# 01_ESP-CAM.net
KiCad netlist of a schematic drawn in Altium Designer
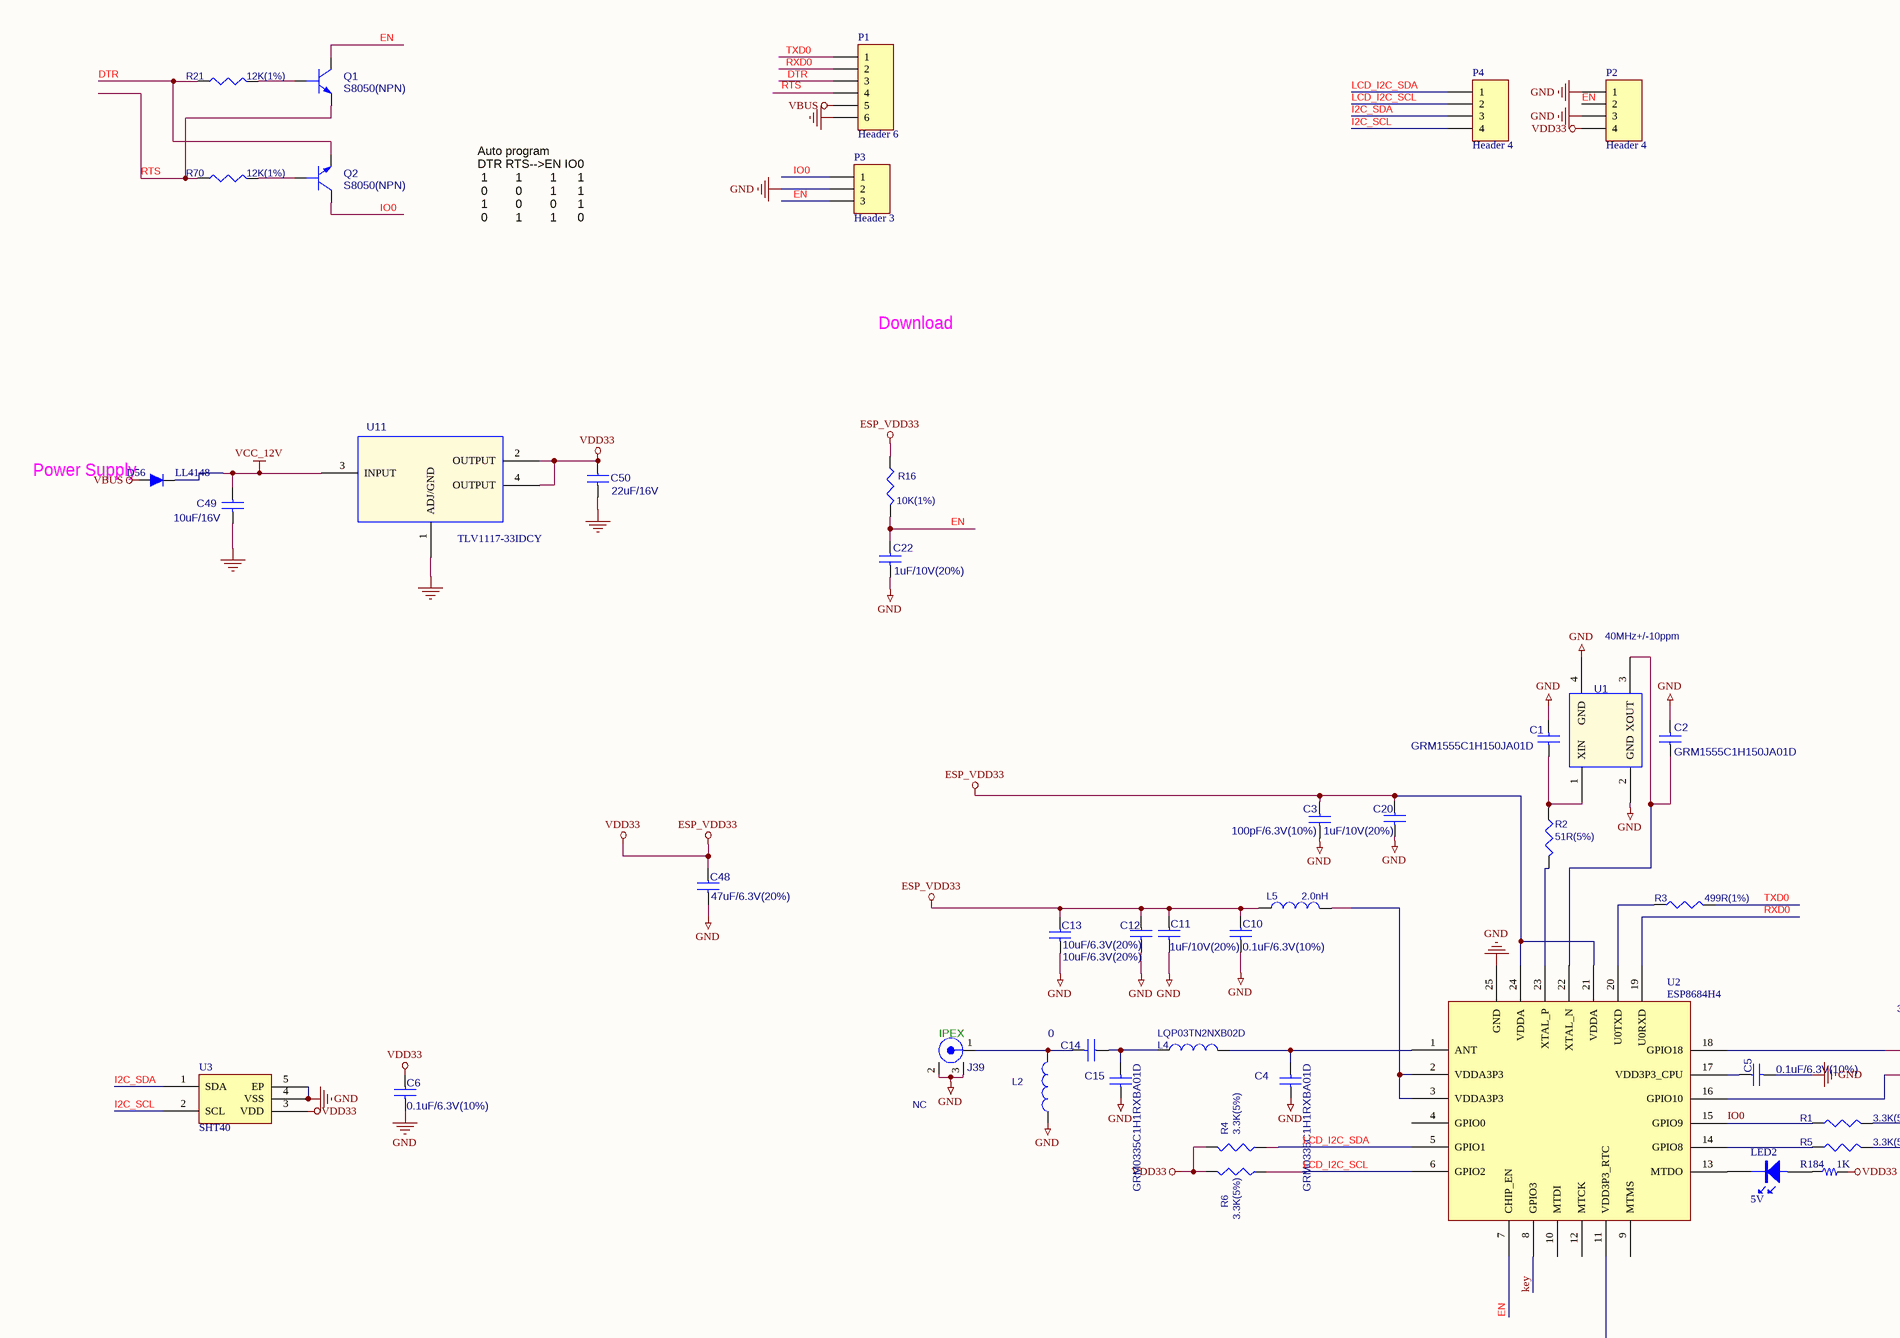
[diagram p0: 01_ESP-CAM.SchDoc, top left]
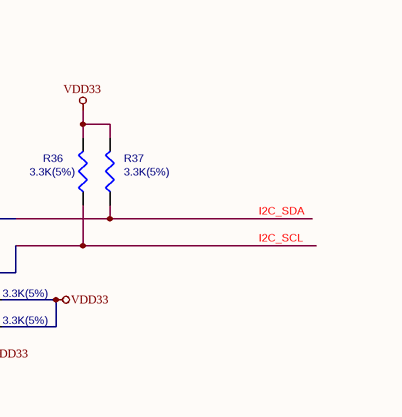
[diagram p1: 01_ESP-CAM.SchDoc, top right]
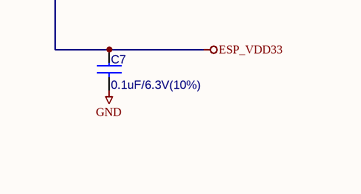
[diagram p2: 01_ESP-CAM.SchDoc, bottom left]
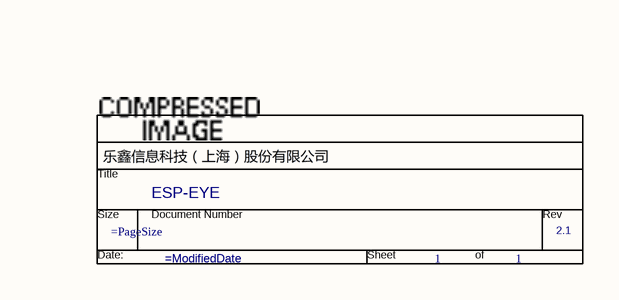
[diagram p3: 01_ESP-CAM.SchDoc, bottom right]

(export (version "E")
  (design (tool "Eeschema 10.0.6"))
  (components
    (comp (ref "*")
      (value "~")
      (fields
        (field (name "REVCODE") "2.1")
        (field (name "TITLE") "ESP-EYE")
        (field (name "PAGE NUMBER") "1")
        (field (name "PAGE COUNT") "1")
      )
      (libsource (lib "*") (part "espTitleBlock1"))
    )
    (comp (ref "C1")
      (value "GRM1555C1H150JA01D")
      (footprint "0402C")
      (fields (field (name "Comment") "CAP NP_Dup1"))
      (libsource (lib "*") (part "CAP NP_Dup1"))
    )
    (comp (ref "C2")
      (value "GRM1555C1H150JA01D")
      (footprint "0402C")
      (fields (field (name "Comment") "CAP NP_Dup1"))
      (libsource (lib "*") (part "CAP NP_Dup1"))
    )
    (comp (ref "C3")
      (value "100pF/6.3V(10%)")
      (footprint "0402C")
      (fields (field (name "Comment") "CAP NP_Dup1"))
      (libsource (lib "*") (part "CAP NP_Dup1"))
    )
    (comp (ref "C4")
      (value "GRM0335C1H1RXBA01D")
      (footprint "0402C")
      (fields (field (name "Comment") "CAP NP_Dup1"))
      (libsource (lib "*") (part "CAP NP_Dup1"))
    )
    (comp (ref "C5")
      (value "0.1uF/6.3V(10%)")
      (footprint "0402C")
      (fields (field (name "Comment") "CAP NP_Dup1"))
      (libsource (lib "*") (part "CAP NP_Dup1"))
    )
    (comp (ref "C6")
      (value "0.1uF/6.3V(10%)")
      (footprint "0402C")
      (fields (field (name "Comment") "CAP NP_Dup1"))
      (libsource (lib "*") (part "CAP NP_Dup1"))
    )
    (comp (ref "C7")
      (value "0.1uF/6.3V(10%)")
      (footprint "0402C")
      (fields (field (name "Comment") "CAP NP_Dup1"))
      (libsource (lib "*") (part "CAP NP_Dup1"))
    )
    (comp (ref "C10")
      (value "0.1uF/6.3V(10%)")
      (footprint "0402C")
      (fields (field (name "Comment") "CAP NP_Dup1"))
      (libsource (lib "*") (part "CAP NP_Dup1"))
    )
    (comp (ref "C11")
      (value "1uF/10V(20%)")
      (footprint "0402C")
      (fields (field (name "Comment") "CAP NP_Dup1"))
      (libsource (lib "*") (part "CAP NP_Dup1"))
    )
    (comp (ref "C12")
      (value "10uF/6.3V(20%)")
      (footprint "0402C")
      (fields (field (name "Comment") "CAP NP_Dup1"))
      (libsource (lib "*") (part "CAP NP_Dup1"))
    )
    (comp (ref "C13")
      (value "10uF/6.3V(20%)")
      (footprint "0402C")
      (fields (field (name "Comment") "CAP NP_Dup1"))
      (libsource (lib "*") (part "CAP NP_Dup1"))
    )
    (comp (ref "C14")
      (value "0")
      (footprint "0402C")
      (fields (field (name "Comment") "CAP NP_Dup1"))
      (libsource (lib "*") (part "CAP NP_Dup1"))
    )
    (comp (ref "C15")
      (value "GRM0335C1H1RXBA01D")
      (footprint "0402C")
      (fields (field (name "Comment") "CAP NP_Dup1"))
      (libsource (lib "*") (part "CAP NP_Dup1"))
    )
    (comp (ref "C20")
      (value "1uF/10V(20%)")
      (footprint "0402C")
      (fields (field (name "Comment") "CAP NP_Dup1"))
      (libsource (lib "*") (part "CAP NP_Dup1"))
    )
    (comp (ref "C22")
      (value "1uF/10V(20%)")
      (footprint "0402C")
      (fields (field (name "Comment") "CAP NP_Dup1"))
      (libsource (lib "*") (part "CAP NP_Dup1"))
    )
    (comp (ref "C48")
      (value "47uF/6.3V(20%)")
      (footprint "1206C")
      (fields (field (name "Comment") "CAP NP_Dup1"))
      (libsource (lib "*") (part "CAP NP_Dup1"))
    )
    (comp (ref "C49")
      (value "10uF/16V")
      (footprint "0603C")
      (fields (field (name "Comment") "CAP NP"))
      (libsource (lib "*") (part "CAP NP"))
    )
    (comp (ref "C50")
      (value "22uF/16V")
      (footprint "1206C")
      (fields (field (name "Comment") "CAP NP"))
      (libsource (lib "*") (part "CAP NP"))
    )
    (comp (ref "D56")
      (value "LL4148")
      (footprint "sod123")
      (description "VISHAY,LL4148,圆柱体MiniMELF100V/2A,ROHS")
      (libsource (lib "Device2018") (part "LL4148"))
    )
    (comp (ref "J39")
      (value "IPEX")
      (footprint "IPEX-SMD_BWIPX-1-001E")
      (fields (field (name "Comment") "IPEX_0"))
      (libsource (lib "*") (part "IPEX_0"))
    )
    (comp (ref "L2")
      (value "NC")
      (footprint "0402R")
      (fields (field (name "Comment") "CHOKE"))
      (libsource (lib "") (part "CHOKE_1"))
    )
    (comp (ref "L4")
      (value "LQP03TN2NXB02D")
      (footprint "0402R")
      (fields (field (name "Comment") "CHOKE"))
      (libsource (lib "*") (part "CHOKE"))
    )
    (comp (ref "L5")
      (value "2.0nH")
      (footprint "0402R")
      (fields (field (name "Comment") "CHOKE"))
      (libsource (lib "") (part "CHOKE_1"))
    )
    (comp (ref "LED2") (value "5V") (footprint "0603LED") (libsource (lib "*") (part "LED")))
    (comp (ref "P1")
      (value "Header 6")
      (footprint "HDR1X6")
      (description "Header, 6-Pin")
      (fields (field (name "PUBLISHER") "Altium Limited"))
      (libsource (lib "Miscellaneous Connectors") (part "Header 6"))
    )
    (comp (ref "P2")
      (value "Header 4")
      (footprint "1.27-4P")
      (description "Header, 4-Pin")
      (fields (field (name "PUBLISHER") "Altium Limited"))
      (libsource (lib "Miscellaneous Connectors") (part "Header 4"))
    )
    (comp (ref "P3")
      (value "Header 3")
      (footprint "HDR1X3")
      (description "Header, 3-Pin")
      (fields (field (name "PUBLISHER") "Altium Limited"))
      (libsource (lib "Miscellaneous Connectors") (part "Header 3"))
    )
    (comp (ref "P4")
      (value "Header 4")
      (footprint "1.27-4P")
      (description "Header, 4-Pin")
      (fields (field (name "PUBLISHER") "Altium Limited"))
      (libsource (lib "Miscellaneous Connectors") (part "Header 4"))
    )
    (comp (ref "Q1")
      (value "S8050(NPN)")
      (footprint "SOT23-3")
      (fields (field (name "Comment") "NPN BCE_2"))
      (libsource (lib "*") (part "NPN BCE_2"))
    )
    (comp (ref "Q2")
      (value "S8050(NPN)")
      (footprint "SOT23-3")
      (fields (field (name "Comment") "NPN BCE_2"))
      (libsource (lib "*") (part "NPN BCE_2"))
    )
    (comp (ref "R1")
      (value "3.3K(5%)")
      (footprint "0402R")
      (fields (field (name "Comment") "RESISTOR_0"))
      (libsource (lib "*") (part "RESISTOR_0"))
    )
    (comp (ref "R2")
      (value "51R(5%)")
      (footprint "0402R")
      (fields (field (name "Comment") "RESISTOR"))
      (libsource (lib "*") (part "RESISTOR"))
    )
    (comp (ref "R3")
      (value "499R(1%)")
      (footprint "0402R")
      (fields (field (name "Comment") "RESISTOR"))
      (libsource (lib "*") (part "RESISTOR"))
    )
    (comp (ref "R4")
      (value "3.3K(5%)")
      (footprint "0402R")
      (fields (field (name "Comment") "RESISTOR_0"))
      (libsource (lib "*") (part "RESISTOR_0"))
    )
    (comp (ref "R5")
      (value "3.3K(5%)")
      (footprint "0402R")
      (fields (field (name "Comment") "RESISTOR_0"))
      (libsource (lib "*") (part "RESISTOR_0"))
    )
    (comp (ref "R6")
      (value "3.3K(5%)")
      (footprint "0402R")
      (fields (field (name "Comment") "RESISTOR_0"))
      (libsource (lib "*") (part "RESISTOR_0"))
    )
    (comp (ref "R16")
      (value "10K(1%)")
      (footprint "0402R")
      (fields (field (name "Comment") "RESISTOR_0"))
      (libsource (lib "*") (part "RESISTOR_0"))
    )
    (comp (ref "R21")
      (value "12K(1%)")
      (footprint "0402R")
      (fields (field (name "Comment") "RESISTOR_0"))
      (libsource (lib "*") (part "RESISTOR_0"))
    )
    (comp (ref "R36")
      (value "3.3K(5%)")
      (footprint "0402R")
      (fields (field (name "Comment") "RESISTOR_0"))
      (libsource (lib "*") (part "RESISTOR_0"))
    )
    (comp (ref "R37")
      (value "3.3K(5%)")
      (footprint "0402R")
      (fields (field (name "Comment") "RESISTOR_0"))
      (libsource (lib "*") (part "RESISTOR_0"))
    )
    (comp (ref "R70")
      (value "12K(1%)")
      (footprint "0402R")
      (fields (field (name "Comment") "RESISTOR_0"))
      (libsource (lib "*") (part "RESISTOR_0"))
    )
    (comp (ref "R184")
      (value "1K")
      (footprint "0603R")
      (description "R")
      (libsource (lib "JRJ_1") (part "R"))
    )
    (comp (ref "U1")
      (value "40MHz+/-10ppm")
      (footprint "XTAL4TN_3225")
      (fields (field (name "Comment") "X1_1"))
      (libsource (lib "*") (part "X1_1"))
    )
    (comp (ref "U2")
      (value "ESP8684H4")
      (footprint "QFN24-MPU6000")
      (libsource (lib "Schlib_20110825") (part "ESP8684H4"))
    )
    (comp (ref "U3") (value "SHT40") (footprint "SH30") (libsource (lib "Schlib_20110825") (part "SHT40")))
    (comp (ref "U11")
      (value "TLV1117-33IDCY")
      (footprint "SOT223")
      (fields (field (name "Comment") "TLV1117"))
      (libsource (lib "*") (part "TLV1117-33IDCY"))
    )
  )
  (nets
    (net (code "1") (name "/DTR") (class "Default")
      (node (ref "P1") (pin "3") (pinfunction "3_3") (pintype "passive"))
      (node (ref "Q2") (pin "2") (pinfunction "E_2") (pintype "passive"))
      (node (ref "R21") (pin "1") (pinfunction "1_1") (pintype "passive"))
    )
    (net (code "2") (name "/EN") (class "Default")
      (node (ref "C22") (pin "1") (pinfunction "1_1") (pintype "passive"))
      (node (ref "P2") (pin "2") (pinfunction "2_2") (pintype "passive"))
      (node (ref "P3") (pin "3") (pinfunction "3_3") (pintype "passive"))
      (node (ref "Q1") (pin "3") (pinfunction "C_3") (pintype "passive"))
      (node (ref "R16") (pin "2") (pinfunction "2_2") (pintype "passive"))
      (node (ref "U2") (pin "7") (pinfunction "CHIP_EN_7") (pintype "passive"))
    )
    (net (code "3") (name "/I2C_SCL") (class "Default")
      (node (ref "P4") (pin "4") (pinfunction "4_4") (pintype "passive"))
      (node (ref "R36") (pin "1") (pinfunction "1_1") (pintype "passive"))
      (node (ref "U2") (pin "16") (pinfunction "GPIO10_16") (pintype "passive"))
      (node (ref "U3") (pin "2") (pinfunction "SCL_2") (pintype "passive"))
    )
    (net (code "4") (name "/I2C_SDA") (class "Default")
      (node (ref "P4") (pin "3") (pinfunction "3_3") (pintype "passive"))
      (node (ref "R37") (pin "1") (pinfunction "1_1") (pintype "passive"))
      (node (ref "U2") (pin "18") (pinfunction "GPIO18_18") (pintype "passive"))
      (node (ref "U3") (pin "1") (pinfunction "SDA_1") (pintype "passive"))
    )
    (net (code "5") (name "/IO0") (class "Default")
      (node (ref "P3") (pin "1") (pinfunction "1_1") (pintype "passive"))
      (node (ref "Q2") (pin "3") (pinfunction "C_3") (pintype "passive"))
      (node (ref "R1") (pin "1") (pinfunction "1_1") (pintype "passive"))
      (node (ref "U2") (pin "15") (pinfunction "GPIO9_15") (pintype "passive"))
    )
    (net (code "6") (name "/LCD_I2C_SCL") (class "Default")
      (node (ref "P4") (pin "2") (pinfunction "2_2") (pintype "passive"))
      (node (ref "R6") (pin "1") (pinfunction "1_1") (pintype "passive"))
      (node (ref "U2") (pin "6") (pinfunction "GPIO2_6") (pintype "passive"))
    )
    (net (code "7") (name "/LCD_I2C_SDA") (class "Default")
      (node (ref "P4") (pin "1") (pinfunction "1_1") (pintype "passive"))
      (node (ref "R4") (pin "1") (pinfunction "1_1") (pintype "passive"))
      (node (ref "U2") (pin "5") (pinfunction "GPIO1_5") (pintype "passive"))
    )
    (net (code "8") (name "/RTS") (class "Default")
      (node (ref "Q1") (pin "2") (pinfunction "E_2") (pintype "passive"))
      (node (ref "R70") (pin "1") (pinfunction "1_1") (pintype "passive"))
    )
    (net (code "9") (name "/RXD0") (class "Default")
      (node (ref "P1") (pin "2") (pinfunction "2_2") (pintype "passive"))
      (node (ref "U2") (pin "19") (pinfunction "U0RXD_19") (pintype "passive"))
    )
    (net (code "10") (name "/TXD0") (class "Default")
      (node (ref "P1") (pin "1") (pinfunction "1_1") (pintype "passive"))
      (node (ref "R3") (pin "2") (pinfunction "2_2") (pintype "passive"))
    )
    (net (code "11") (name "/key") (class "Default")
      (node (ref "U2") (pin "8") (pinfunction "GPIO3_8") (pintype "passive"))
    )
    (net (code "12") (name "ESP_VDD33") (class "Default")
      (node (ref "C10") (pin "1") (pinfunction "1_1") (pintype "passive"))
      (node (ref "C11") (pin "1") (pinfunction "1_1") (pintype "passive"))
      (node (ref "C12") (pin "1") (pinfunction "1_1") (pintype "passive"))
      (node (ref "C13") (pin "1") (pinfunction "1_1") (pintype "passive"))
      (node (ref "C20") (pin "1") (pinfunction "1_1") (pintype "passive"))
      (node (ref "C3") (pin "1") (pinfunction "1_1") (pintype "passive"))
      (node (ref "C48") (pin "1") (pinfunction "1_1") (pintype "passive"))
      (node (ref "C50") (pin "1") (pinfunction "1_1") (pintype "passive"))
      (node (ref "C6") (pin "1") (pinfunction "1_1") (pintype "passive"))
      (node (ref "C7") (pin "1") (pinfunction "1_1") (pintype "passive"))
      (node (ref "L5") (pin "2") (pinfunction "2_2") (pintype "passive"))
      (node (ref "P2") (pin "4") (pinfunction "4_4") (pintype "passive"))
      (node (ref "R1") (pin "2") (pinfunction "2_2") (pintype "passive"))
      (node (ref "R16") (pin "1") (pinfunction "1_1") (pintype "passive"))
      (node (ref "R184") (pin "2") (pintype "passive"))
      (node (ref "R36") (pin "2") (pinfunction "2_2") (pintype "passive"))
      (node (ref "R37") (pin "2") (pinfunction "2_2") (pintype "passive"))
      (node (ref "R4") (pin "2") (pinfunction "2_2") (pintype "passive"))
      (node (ref "R5") (pin "2") (pinfunction "2_2") (pintype "passive"))
      (node (ref "R6") (pin "2") (pinfunction "2_2") (pintype "passive"))
      (node (ref "U11") (pin "2") (pinfunction "OUTPUT_2") (pintype "power_in"))
      (node (ref "U11") (pin "4") (pinfunction "OUTPUT_4") (pintype "power_in"))
      (node (ref "U2") (pin "11") (pinfunction "VDD3P3_RTC_11") (pintype "passive"))
      (node (ref "U2") (pin "21") (pinfunction "VDDA_21") (pintype "passive"))
      (node (ref "U2") (pin "24") (pinfunction "VDDA_24") (pintype "passive"))
      (node (ref "U3") (pin "3") (pinfunction "VDD_3") (pintype "passive"))
    )
    (net (code "13") (name "GND") (class "Default")
      (node (ref "C1") (pin "2") (pinfunction "2_2") (pintype "passive"))
      (node (ref "C10") (pin "2") (pinfunction "2_2") (pintype "passive"))
      (node (ref "C11") (pin "2") (pinfunction "2_2") (pintype "passive"))
      (node (ref "C12") (pin "2") (pinfunction "2_2") (pintype "passive"))
      (node (ref "C13") (pin "2") (pinfunction "2_2") (pintype "passive"))
      (node (ref "C15") (pin "1") (pinfunction "1_1") (pintype "passive"))
      (node (ref "C2") (pin "2") (pinfunction "2_2") (pintype "passive"))
      (node (ref "C20") (pin "2") (pinfunction "2_2") (pintype "passive"))
      (node (ref "C22") (pin "2") (pinfunction "2_2") (pintype "passive"))
      (node (ref "C3") (pin "2") (pinfunction "2_2") (pintype "passive"))
      (node (ref "C4") (pin "1") (pinfunction "1_1") (pintype "passive"))
      (node (ref "C48") (pin "2") (pinfunction "2_2") (pintype "passive"))
      (node (ref "C49") (pin "2") (pinfunction "2_2") (pintype "passive"))
      (node (ref "C5") (pin "2") (pinfunction "2_2") (pintype "passive"))
      (node (ref "C50") (pin "2") (pinfunction "2_2") (pintype "passive"))
      (node (ref "C6") (pin "2") (pinfunction "2_2") (pintype "passive"))
      (node (ref "C7") (pin "2") (pinfunction "2_2") (pintype "passive"))
      (node (ref "J39") (pin "2") (pinfunction "GND1_2") (pintype "passive"))
      (node (ref "J39") (pin "3") (pinfunction "GND2_3") (pintype "passive"))
      (node (ref "L2") (pin "2") (pinfunction "2_2") (pintype "passive"))
      (node (ref "P1") (pin "6") (pinfunction "6_6") (pintype "passive"))
      (node (ref "P2") (pin "1") (pinfunction "1_1") (pintype "passive"))
      (node (ref "P2") (pin "3") (pinfunction "3_3") (pintype "passive"))
      (node (ref "P3") (pin "2") (pinfunction "2_2") (pintype "passive"))
      (node (ref "U1") (pin "2") (pinfunction "GND_2") (pintype "power_in"))
      (node (ref "U1") (pin "4") (pinfunction "GND_4") (pintype "power_in"))
      (node (ref "U11") (pin "1") (pinfunction "ADJ/GND_1") (pintype "passive"))
      (node (ref "U2") (pin "25") (pinfunction "GND_25") (pintype "passive"))
      (node (ref "U3") (pin "4") (pinfunction "VSS_4") (pintype "passive"))
      (node (ref "U3") (pin "5") (pinfunction "EP_5") (pintype "passive"))
    )
    (net (code "14") (name "Net-(C14-Pad1)") (class "Default")
      (node (ref "C14") (pin "1") (pinfunction "1_1") (pintype "passive"))
      (node (ref "C15") (pin "2") (pinfunction "2_2") (pintype "passive"))
      (node (ref "L4") (pin "2") (pinfunction "2_2") (pintype "passive"))
    )
    (net (code "15") (name "Net-(J39-RF)") (class "Default")
      (node (ref "C14") (pin "2") (pinfunction "2_2") (pintype "passive"))
      (node (ref "J39") (pin "1") (pinfunction "RF_1") (pintype "passive"))
      (node (ref "L2") (pin "1") (pinfunction "1_1") (pintype "passive"))
    )
    (net (code "16") (name "Net-(L5-Pad1)") (class "Default")
      (node (ref "L5") (pin "1") (pinfunction "1_1") (pintype "passive"))
      (node (ref "U2") (pin "2") (pinfunction "VDDA3P3_2") (pintype "passive"))
      (node (ref "U2") (pin "3") (pinfunction "VDDA3P3_3") (pintype "passive"))
    )
    (net (code "17") (name "Net-(LED2-Pad1)") (class "Default")
      (node (ref "LED2") (pin "1") (pinfunction "1_1") (pintype "passive"))
      (node (ref "R184") (pin "1") (pintype "passive"))
    )
    (net (code "18") (name "Net-(Q1-B)") (class "Default")
      (node (ref "Q1") (pin "1") (pinfunction "B_1") (pintype "passive"))
      (node (ref "R21") (pin "2") (pinfunction "2_2") (pintype "passive"))
    )
    (net (code "19") (name "Net-(Q2-B)") (class "Default")
      (node (ref "Q2") (pin "1") (pinfunction "B_1") (pintype "passive"))
      (node (ref "R70") (pin "2") (pinfunction "2_2") (pintype "passive"))
    )
    (net (code "20") (name "Net-(U1-XIN)") (class "Default")
      (node (ref "C1") (pin "1") (pinfunction "1_1") (pintype "passive"))
      (node (ref "R2") (pin "1") (pinfunction "1_1") (pintype "passive"))
      (node (ref "U1") (pin "1") (pinfunction "XIN_1") (pintype "passive"))
    )
    (net (code "21") (name "Net-(U1-XOUT)") (class "Default")
      (node (ref "C2") (pin "1") (pinfunction "1_1") (pintype "passive"))
      (node (ref "U1") (pin "3") (pinfunction "XOUT_3") (pintype "passive"))
      (node (ref "U2") (pin "22") (pinfunction "XTAL_N_22") (pintype "passive"))
    )
    (net (code "22") (name "Net-(U2-ANT)") (class "Default")
      (node (ref "C4") (pin "2") (pinfunction "2_2") (pintype "passive"))
      (node (ref "L4") (pin "1") (pinfunction "1_1") (pintype "passive"))
      (node (ref "U2") (pin "1") (pinfunction "ANT_1") (pintype "passive"))
    )
    (net (code "23") (name "Net-(U2-GPIO8)") (class "Default")
      (node (ref "R5") (pin "1") (pinfunction "1_1") (pintype "passive"))
      (node (ref "U2") (pin "14") (pinfunction "GPIO8_14") (pintype "passive"))
    )
    (net (code "24") (name "Net-(U2-MTDO)") (class "Default")
      (node (ref "LED2") (pin "2") (pinfunction "2_2") (pintype "passive"))
      (node (ref "U2") (pin "13") (pinfunction "MTDO_13") (pintype "passive"))
    )
    (net (code "25") (name "Net-(U2-U0TXD)") (class "Default")
      (node (ref "R3") (pin "1") (pinfunction "1_1") (pintype "passive"))
      (node (ref "U2") (pin "20") (pinfunction "U0TXD_20") (pintype "passive"))
    )
    (net (code "26") (name "Net-(U2-VDD3P3_CPU)") (class "Default")
      (node (ref "C5") (pin "1") (pinfunction "1_1") (pintype "passive"))
      (node (ref "U2") (pin "17") (pinfunction "VDD3P3_CPU_17") (pintype "passive"))
    )
    (net (code "27") (name "Net-(U2-XTAL_P)") (class "Default")
      (node (ref "R2") (pin "2") (pinfunction "2_2") (pintype "passive"))
      (node (ref "U2") (pin "23") (pinfunction "XTAL_P_23") (pintype "passive"))
    )
    (net (code "28") (name "VBUS") (class "Default")
      (node (ref "D56") (pin "2") (pinfunction "2_2") (pintype "passive"))
      (node (ref "P1") (pin "5") (pinfunction "5_5") (pintype "passive"))
    )
    (net (code "29") (name "VCC_12V") (class "Default")
      (node (ref "C49") (pin "1") (pinfunction "1_1") (pintype "passive"))
      (node (ref "D56") (pin "1") (pinfunction "1_1") (pintype "passive"))
      (node (ref "U11") (pin "3") (pinfunction "INPUT_3") (pintype "passive"))
    )
    (net (code "30") (name "unconnected-(P1-Pad4)") (class "Default")
      (node (ref "P1") (pin "4") (pinfunction "4_4") (pintype "passive"))
    )
    (net (code "31") (name "unconnected-(U2-GPIO0-Pad4)") (class "Default")
      (node (ref "U2") (pin "4") (pinfunction "GPIO0_4") (pintype "passive"))
    )
    (net (code "32") (name "unconnected-(U2-MTCK-Pad12)") (class "Default")
      (node (ref "U2") (pin "12") (pinfunction "MTCK_12") (pintype "passive"))
    )
    (net (code "33") (name "unconnected-(U2-MTDI-Pad10)") (class "Default")
      (node (ref "U2") (pin "10") (pinfunction "MTDI_10") (pintype "passive"))
    )
    (net (code "34") (name "unconnected-(U2-MTMS-Pad9)") (class "Default")
      (node (ref "U2") (pin "9") (pinfunction "MTMS_9") (pintype "passive"))
    )
  )
)
